# USART_LPUART.net
KiCad netlist of a schematic drawn in Altium Designer
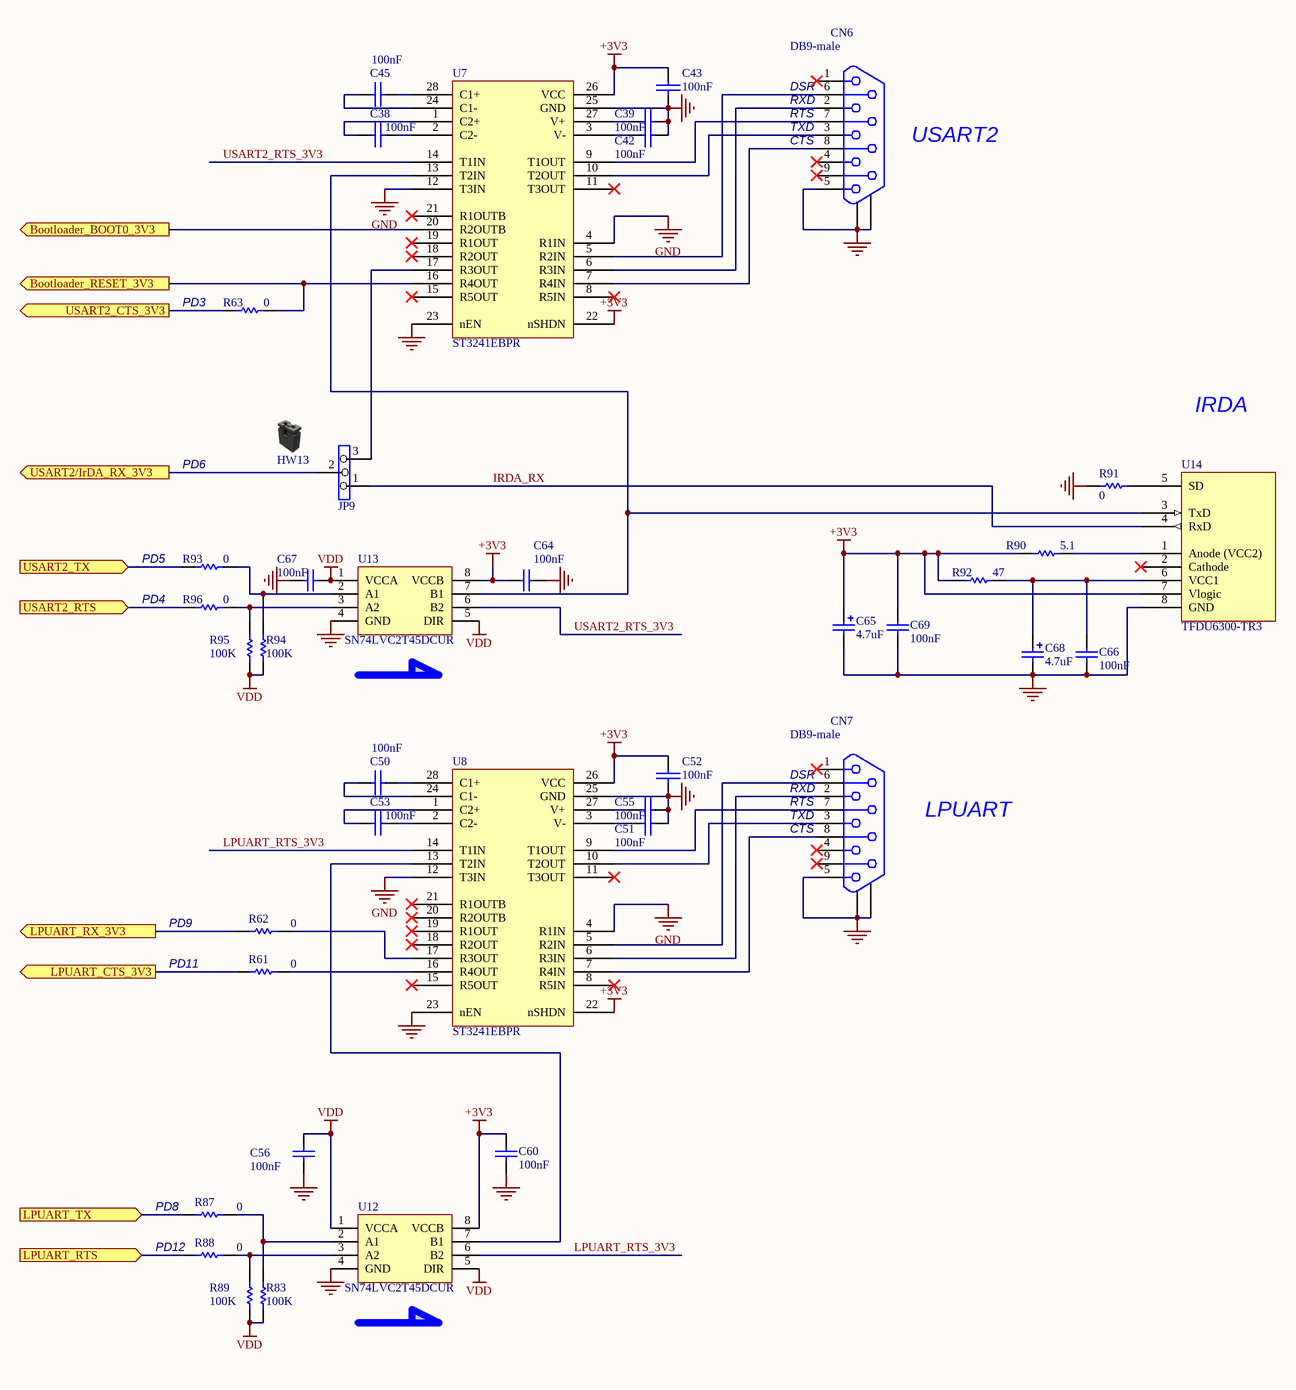
[diagram p0: USART_LPUART.SchDoc]

(export (version "E")
  (design (tool "Eeschema 10.0.6"))
  (components
    (comp (ref "C38")
      (value "100nF")
      (footprint "0402C")
      (description "Capacitor")
      (libsource (lib "*") (part "CAP"))
    )
    (comp (ref "C39")
      (value "100nF")
      (footprint "0402C")
      (description "Capacitor")
      (libsource (lib "*") (part "CAP"))
    )
    (comp (ref "C42")
      (value "100nF")
      (footprint "0402C")
      (description "Capacitor")
      (libsource (lib "*") (part "CAP"))
    )
    (comp (ref "C43")
      (value "100nF")
      (footprint "0402C")
      (description "Capacitor")
      (libsource (lib "*") (part "CAP"))
    )
    (comp (ref "C45")
      (value "100nF")
      (footprint "0402C")
      (description "Capacitor")
      (libsource (lib "*") (part "CAP"))
    )
    (comp (ref "C50")
      (value "100nF")
      (footprint "0402C")
      (description "Capacitor")
      (libsource (lib "*") (part "CAP"))
    )
    (comp (ref "C51")
      (value "100nF")
      (footprint "0402C")
      (description "Capacitor")
      (libsource (lib "*") (part "CAP"))
    )
    (comp (ref "C52")
      (value "100nF")
      (footprint "0402C")
      (description "Capacitor")
      (libsource (lib "*") (part "CAP"))
    )
    (comp (ref "C53")
      (value "100nF")
      (footprint "0402C")
      (description "Capacitor")
      (libsource (lib "*") (part "CAP"))
    )
    (comp (ref "C55")
      (value "100nF")
      (footprint "0402C")
      (description "Capacitor")
      (libsource (lib "*") (part "CAP"))
    )
    (comp (ref "C56")
      (value "100nF")
      (footprint "0402C")
      (description "Capacitor")
      (fields (field (name "PUBLISHER") "Altium Limited"))
      (libsource (lib "Miscellaneous Devices") (part "CAP"))
    )
    (comp (ref "C60")
      (value "100nF")
      (footprint "0402C")
      (description "Capacitor")
      (fields (field (name "PUBLISHER") "Altium Limited"))
      (libsource (lib "Miscellaneous Devices") (part "CAP"))
    )
    (comp (ref "C64")
      (value "100nF")
      (footprint "0402C")
      (description "Capacitor")
      (fields (field (name "PUBLISHER") "Altium Limited"))
      (libsource (lib "Miscellaneous Devices") (part "CAP"))
    )
    (comp (ref "C65")
      (value "4.7uF")
      (footprint "TAN-A")
      (description "Polarized Capacitor (Radial)")
      (fields (field (name "PUBLISHER") "Altium Limited"))
      (libsource (lib "Miscellaneous Devices") (part "Cap Pol1"))
    )
    (comp (ref "C66")
      (value "100nF")
      (footprint "0402C")
      (description "Capacitor")
      (fields (field (name "PUBLISHER") "Altium Limited"))
      (libsource (lib "Miscellaneous Devices") (part "CAP"))
    )
    (comp (ref "C67")
      (value "100nF")
      (footprint "0402C")
      (description "Capacitor")
      (fields (field (name "PUBLISHER") "Altium Limited"))
      (libsource (lib "Miscellaneous Devices") (part "CAP"))
    )
    (comp (ref "C68")
      (value "4.7uF")
      (footprint "TAN-A")
      (description "Polarized Capacitor (Radial)")
      (fields (field (name "PUBLISHER") "Altium Limited"))
      (libsource (lib "Miscellaneous Devices") (part "Cap Pol1"))
    )
    (comp (ref "C69")
      (value "100nF")
      (footprint "0402C")
      (description "Capacitor")
      (fields (field (name "PUBLISHER") "Altium Limited"))
      (libsource (lib "Miscellaneous Devices") (part "CAP"))
    )
    (comp (ref "CN6") (value "DB9-male") (footprint "DB9/M") (libsource (lib "MB1070") (part "DB9")))
    (comp (ref "CN7") (value "DB9-male") (footprint "DB9/M") (libsource (lib "MB1070") (part "DB9")))
    (comp (ref "HW13") (value "Shunt Black 2.54mm") (libsource (lib "MB1168") (part "Shunt Black 2.54mm")))
    (comp (ref "JP9") (value "~") (footprint "SIP3") (libsource (lib "STR910_SCHLIB") (part "Jumper3")))
    (comp (ref "R61")
      (value "0")
      (footprint "0603R")
      (description "Resistor")
      (fields (field (name "PUBLISHER") "Altium Limited"))
      (libsource (lib "Miscellaneous Devices") (part "Res1"))
    )
    (comp (ref "R62")
      (value "0")
      (footprint "0603R")
      (description "Resistor")
      (fields (field (name "PUBLISHER") "Altium Limited"))
      (libsource (lib "Miscellaneous Devices") (part "Res1"))
    )
    (comp (ref "R63")
      (value "0")
      (footprint "0603R")
      (description "Resistor")
      (fields (field (name "PUBLISHER") "Altium Limited"))
      (libsource (lib "Miscellaneous Devices") (part "Res1"))
    )
    (comp (ref "R83")
      (value "100K")
      (footprint "0402R")
      (description "Resistor")
      (fields (field (name "PUBLISHER") "Altium Limited"))
      (libsource (lib "Miscellaneous Devices") (part "Res1"))
    )
    (comp (ref "R87")
      (value "0")
      (footprint "0603R")
      (description "Resistor")
      (fields (field (name "PUBLISHER") "Altium Limited"))
      (libsource (lib "Miscellaneous Devices") (part "Res1"))
    )
    (comp (ref "R88")
      (value "0")
      (footprint "0603R")
      (description "Resistor")
      (fields (field (name "PUBLISHER") "Altium Limited"))
      (libsource (lib "Miscellaneous Devices") (part "Res1"))
    )
    (comp (ref "R89")
      (value "100K")
      (footprint "0402R")
      (description "Resistor")
      (fields (field (name "PUBLISHER") "Altium Limited"))
      (libsource (lib "Miscellaneous Devices") (part "Res1"))
    )
    (comp (ref "R90")
      (value "5.1")
      (footprint "0402R")
      (description "Resistor")
      (fields (field (name "PUBLISHER") "Altium Limited"))
      (libsource (lib "Miscellaneous Devices") (part "Res1"))
    )
    (comp (ref "R91")
      (value "0")
      (footprint "0603R")
      (description "Resistor")
      (fields (field (name "PUBLISHER") "Altium Limited"))
      (libsource (lib "Miscellaneous Devices") (part "Res1"))
    )
    (comp (ref "R92")
      (value "47")
      (footprint "0402R")
      (description "Resistor")
      (fields (field (name "PUBLISHER") "Altium Limited"))
      (libsource (lib "Miscellaneous Devices") (part "Res1"))
    )
    (comp (ref "R93")
      (value "0")
      (footprint "0603R")
      (description "Resistor")
      (fields (field (name "PUBLISHER") "Altium Limited"))
      (libsource (lib "Miscellaneous Devices") (part "Res1"))
    )
    (comp (ref "R94")
      (value "100K")
      (footprint "0402R")
      (description "Resistor")
      (fields (field (name "PUBLISHER") "Altium Limited"))
      (libsource (lib "Miscellaneous Devices") (part "Res1"))
    )
    (comp (ref "R95")
      (value "100K")
      (footprint "0402R")
      (description "Resistor")
      (fields (field (name "PUBLISHER") "Altium Limited"))
      (libsource (lib "Miscellaneous Devices") (part "Res1"))
    )
    (comp (ref "R96")
      (value "0")
      (footprint "0603R")
      (description "Resistor")
      (fields (field (name "PUBLISHER") "Altium Limited"))
      (libsource (lib "Miscellaneous Devices") (part "Res1"))
    )
    (comp (ref "U7")
      (value "ST3241EBPR")
      (footprint "SSOP28_0R65_10R2X7R8")
      (libsource (lib "*") (part "ST3241"))
    )
    (comp (ref "U8")
      (value "ST3241EBPR")
      (footprint "SSOP28_0R65_10R2X7R8")
      (libsource (lib "*") (part "ST3241"))
    )
    (comp (ref "U12")
      (value "SN74LVC2T45DCUR")
      (footprint "USOP8_0R5_2X3R1")
      (libsource (lib "MB818") (part "SN74LVC2T45DCUT"))
    )
    (comp (ref "U13")
      (value "SN74LVC2T45DCUR")
      (footprint "USOP8_0R5_2X3R1")
      (libsource (lib "MB818") (part "SN74LVC2T45DCUT"))
    )
    (comp (ref "U14")
      (value "TFDU6300-TR3")
      (footprint "IR_VISHAY3")
      (description "TFDU4300")
      (libsource (lib "*") (part "TFDU4300"))
    )
  )
  (nets
    (net (code "1") (name "+3V3") (class "Default")
      (node (ref "C43") (pin "2") (pinfunction "2_2") (pintype "passive"))
      (node (ref "C52") (pin "2") (pinfunction "2_2") (pintype "passive"))
      (node (ref "C60") (pin "2") (pinfunction "2_2") (pintype "passive"))
      (node (ref "C64") (pin "2") (pinfunction "2_2") (pintype "passive"))
      (node (ref "C65") (pin "1") (pinfunction "1_1") (pintype "passive"))
      (node (ref "C69") (pin "2") (pinfunction "2_2") (pintype "passive"))
      (node (ref "R90") (pin "1") (pinfunction "1_1") (pintype "passive"))
      (node (ref "R92") (pin "1") (pinfunction "1_1") (pintype "passive"))
      (node (ref "U12") (pin "8") (pinfunction "VCCB_8") (pintype "passive"))
      (node (ref "U13") (pin "8") (pinfunction "VCCB_8") (pintype "passive"))
      (node (ref "U14") (pin "7") (pinfunction "Vlogic_7") (pintype "passive"))
      (node (ref "U7") (pin "22") (pinfunction "nSHDN_22") (pintype "passive"))
      (node (ref "U7") (pin "26") (pinfunction "VCC_26") (pintype "passive"))
      (node (ref "U8") (pin "22") (pinfunction "nSHDN_22") (pintype "passive"))
      (node (ref "U8") (pin "26") (pinfunction "VCC_26") (pintype "passive"))
    )
    (net (code "2") (name "/Bootloader_BOOT0_3V3") (class "Default")
      (node (ref "U7") (pin "20") (pinfunction "R2OUTB_20") (pintype "passive"))
    )
    (net (code "3") (name "/Bootloader_RESET_3V3") (class "Default")
      (node (ref "R63") (pin "1") (pinfunction "1_1") (pintype "passive"))
      (node (ref "U7") (pin "16") (pinfunction "R4OUT_16") (pintype "passive"))
    )
    (net (code "4") (name "/IRDA_RX") (class "Default")
      (node (ref "JP9") (pin "1") (pintype "passive"))
      (node (ref "U14") (pin "4") (pinfunction "RxD_4") (pintype "output"))
    )
    (net (code "5") (name "/LPUART_CTS_3V3") (class "Default")
      (node (ref "R61") (pin "1") (pinfunction "1_1") (pintype "passive"))
    )
    (net (code "6") (name "/LPUART_RTS") (class "Default")
      (node (ref "R88") (pin "1") (pinfunction "1_1") (pintype "passive"))
    )
    (net (code "7") (name "/LPUART_RTS_3V3") (class "Default")
      (node (ref "U12") (pin "6") (pinfunction "B2_6") (pintype "passive"))
      (node (ref "U8") (pin "14") (pinfunction "T1IN_14") (pintype "passive"))
    )
    (net (code "8") (name "/LPUART_RX_3V3") (class "Default")
      (node (ref "R62") (pin "1") (pinfunction "1_1") (pintype "passive"))
    )
    (net (code "9") (name "/LPUART_TX") (class "Default")
      (node (ref "R87") (pin "1") (pinfunction "1_1") (pintype "passive"))
    )
    (net (code "10") (name "/USART2_CTS_3V3") (class "Default")
      (node (ref "R63") (pin "2") (pinfunction "2_2") (pintype "passive"))
    )
    (net (code "11") (name "/USART2_RTS") (class "Default")
      (node (ref "R96") (pin "2") (pinfunction "2_2") (pintype "passive"))
    )
    (net (code "12") (name "/USART2_RTS_3V3") (class "Default")
      (node (ref "U13") (pin "6") (pinfunction "B2_6") (pintype "passive"))
      (node (ref "U7") (pin "14") (pinfunction "T1IN_14") (pintype "passive"))
    )
    (net (code "13") (name "/USART2_TX") (class "Default")
      (node (ref "R93") (pin "2") (pinfunction "2_2") (pintype "passive"))
    )
    (net (code "14") (name "/USART2{slash}IrDA_RX_3V3") (class "Default")
      (node (ref "JP9") (pin "2") (pintype "passive"))
    )
    (net (code "15") (name "GND") (class "Default")
      (node (ref "C39") (pin "2") (pinfunction "2_2") (pintype "passive"))
      (node (ref "C42") (pin "2") (pinfunction "2_2") (pintype "passive"))
      (node (ref "C43") (pin "1") (pinfunction "1_1") (pintype "passive"))
      (node (ref "C51") (pin "2") (pinfunction "2_2") (pintype "passive"))
      (node (ref "C52") (pin "1") (pinfunction "1_1") (pintype "passive"))
      (node (ref "C55") (pin "2") (pinfunction "2_2") (pintype "passive"))
      (node (ref "C56") (pin "1") (pinfunction "1_1") (pintype "passive"))
      (node (ref "C60") (pin "1") (pinfunction "1_1") (pintype "passive"))
      (node (ref "C64") (pin "1") (pinfunction "1_1") (pintype "passive"))
      (node (ref "C65") (pin "2") (pinfunction "2_2") (pintype "passive"))
      (node (ref "C66") (pin "1") (pinfunction "1_1") (pintype "passive"))
      (node (ref "C67") (pin "1") (pinfunction "1_1") (pintype "passive"))
      (node (ref "C68") (pin "2") (pinfunction "2_2") (pintype "passive"))
      (node (ref "C69") (pin "1") (pinfunction "1_1") (pintype "passive"))
      (node (ref "CN6") (pin "10") (pinfunction "10_10") (pintype "passive"))
      (node (ref "CN6") (pin "11") (pinfunction "11_11") (pintype "passive"))
      (node (ref "CN6") (pin "5") (pinfunction "5_5") (pintype "passive"))
      (node (ref "CN7") (pin "10") (pinfunction "10_10") (pintype "passive"))
      (node (ref "CN7") (pin "11") (pinfunction "11_11") (pintype "passive"))
      (node (ref "CN7") (pin "5") (pinfunction "5_5") (pintype "passive"))
      (node (ref "R91") (pin "2") (pinfunction "2_2") (pintype "passive"))
      (node (ref "U12") (pin "4") (pinfunction "GND_4") (pintype "passive"))
      (node (ref "U13") (pin "4") (pinfunction "GND_4") (pintype "passive"))
      (node (ref "U14") (pin "8") (pinfunction "GND_8") (pintype "passive"))
      (node (ref "U7") (pin "12") (pinfunction "T3IN_12") (pintype "passive"))
      (node (ref "U7") (pin "23") (pinfunction "nEN_23") (pintype "passive"))
      (node (ref "U7") (pin "25") (pinfunction "GND_25") (pintype "passive"))
      (node (ref "U7") (pin "4") (pinfunction "R1IN_4") (pintype "passive"))
      (node (ref "U8") (pin "12") (pinfunction "T3IN_12") (pintype "passive"))
      (node (ref "U8") (pin "23") (pinfunction "nEN_23") (pintype "passive"))
      (node (ref "U8") (pin "25") (pinfunction "GND_25") (pintype "passive"))
      (node (ref "U8") (pin "4") (pinfunction "R1IN_4") (pintype "passive"))
    )
    (net (code "16") (name "Net-(U7-C1+)") (class "Default")
      (node (ref "C45") (pin "2") (pinfunction "2_2") (pintype "passive"))
      (node (ref "U7") (pin "28") (pinfunction "C1+_28") (pintype "passive"))
    )
    (net (code "17") (name "Net-(U7-C1-)") (class "Default")
      (node (ref "C45") (pin "1") (pinfunction "1_1") (pintype "passive"))
      (node (ref "U7") (pin "24") (pinfunction "C1-_24") (pintype "passive"))
    )
    (net (code "18") (name "Net-(U7-C2+)") (class "Default")
      (node (ref "C38") (pin "1") (pinfunction "1_1") (pintype "passive"))
      (node (ref "U7") (pin "1") (pinfunction "C2+_1") (pintype "passive"))
    )
    (net (code "19") (name "Net-(U7-C2-)") (class "Default")
      (node (ref "C38") (pin "2") (pinfunction "2_2") (pintype "passive"))
      (node (ref "U7") (pin "2") (pinfunction "C2-_2") (pintype "passive"))
    )
    (net (code "20") (name "Net-(U7-R2IN)") (class "Default")
      (node (ref "CN6") (pin "6") (pinfunction "6_6") (pintype "passive"))
      (node (ref "U7") (pin "5") (pinfunction "R2IN_5") (pintype "passive"))
    )
    (net (code "21") (name "Net-(U7-R3IN)") (class "Default")
      (node (ref "CN6") (pin "2") (pinfunction "2_2") (pintype "passive"))
      (node (ref "U7") (pin "6") (pinfunction "R3IN_6") (pintype "passive"))
    )
    (net (code "22") (name "Net-(U7-R3OUT)") (class "Default")
      (node (ref "JP9") (pin "3") (pintype "passive"))
      (node (ref "U7") (pin "17") (pinfunction "R3OUT_17") (pintype "passive"))
    )
    (net (code "23") (name "Net-(U7-R4IN)") (class "Default")
      (node (ref "CN6") (pin "8") (pinfunction "8_8") (pintype "passive"))
      (node (ref "U7") (pin "7") (pinfunction "R4IN_7") (pintype "passive"))
    )
    (net (code "24") (name "Net-(U7-T1OUT)") (class "Default")
      (node (ref "CN6") (pin "7") (pinfunction "7_7") (pintype "passive"))
      (node (ref "U7") (pin "9") (pinfunction "T1OUT_9") (pintype "passive"))
    )
    (net (code "25") (name "Net-(U7-T2OUT)") (class "Default")
      (node (ref "CN6") (pin "3") (pinfunction "3_3") (pintype "passive"))
      (node (ref "U7") (pin "10") (pinfunction "T2OUT_10") (pintype "passive"))
    )
    (net (code "26") (name "Net-(U7-V+)") (class "Default")
      (node (ref "C39") (pin "1") (pinfunction "1_1") (pintype "passive"))
      (node (ref "U7") (pin "27") (pinfunction "V+_27") (pintype "passive"))
    )
    (net (code "27") (name "Net-(U7-V-)") (class "Default")
      (node (ref "C42") (pin "1") (pinfunction "1_1") (pintype "passive"))
      (node (ref "U7") (pin "3") (pinfunction "V-_3") (pintype "passive"))
    )
    (net (code "28") (name "Net-(U8-C1+)") (class "Default")
      (node (ref "C50") (pin "2") (pinfunction "2_2") (pintype "passive"))
      (node (ref "U8") (pin "28") (pinfunction "C1+_28") (pintype "passive"))
    )
    (net (code "29") (name "Net-(U8-C1-)") (class "Default")
      (node (ref "C50") (pin "1") (pinfunction "1_1") (pintype "passive"))
      (node (ref "U8") (pin "24") (pinfunction "C1-_24") (pintype "passive"))
    )
    (net (code "30") (name "Net-(U8-C2+)") (class "Default")
      (node (ref "C53") (pin "1") (pinfunction "1_1") (pintype "passive"))
      (node (ref "U8") (pin "1") (pinfunction "C2+_1") (pintype "passive"))
    )
    (net (code "31") (name "Net-(U8-C2-)") (class "Default")
      (node (ref "C53") (pin "2") (pinfunction "2_2") (pintype "passive"))
      (node (ref "U8") (pin "2") (pinfunction "C2-_2") (pintype "passive"))
    )
    (net (code "32") (name "Net-(U8-R2IN)") (class "Default")
      (node (ref "CN7") (pin "6") (pinfunction "6_6") (pintype "passive"))
      (node (ref "U8") (pin "5") (pinfunction "R2IN_5") (pintype "passive"))
    )
    (net (code "33") (name "Net-(U8-R3IN)") (class "Default")
      (node (ref "CN7") (pin "2") (pinfunction "2_2") (pintype "passive"))
      (node (ref "U8") (pin "6") (pinfunction "R3IN_6") (pintype "passive"))
    )
    (net (code "34") (name "Net-(U8-R3OUT)") (class "Default")
      (node (ref "R62") (pin "2") (pinfunction "2_2") (pintype "passive"))
      (node (ref "U8") (pin "17") (pinfunction "R3OUT_17") (pintype "passive"))
    )
    (net (code "35") (name "Net-(U8-R4IN)") (class "Default")
      (node (ref "CN7") (pin "8") (pinfunction "8_8") (pintype "passive"))
      (node (ref "U8") (pin "7") (pinfunction "R4IN_7") (pintype "passive"))
    )
    (net (code "36") (name "Net-(U8-R4OUT)") (class "Default")
      (node (ref "R61") (pin "2") (pinfunction "2_2") (pintype "passive"))
      (node (ref "U8") (pin "16") (pinfunction "R4OUT_16") (pintype "passive"))
    )
    (net (code "37") (name "Net-(U8-T1OUT)") (class "Default")
      (node (ref "CN7") (pin "7") (pinfunction "7_7") (pintype "passive"))
      (node (ref "U8") (pin "9") (pinfunction "T1OUT_9") (pintype "passive"))
    )
    (net (code "38") (name "Net-(U8-T2OUT)") (class "Default")
      (node (ref "CN7") (pin "3") (pinfunction "3_3") (pintype "passive"))
      (node (ref "U8") (pin "10") (pinfunction "T2OUT_10") (pintype "passive"))
    )
    (net (code "39") (name "Net-(U8-V+)") (class "Default")
      (node (ref "C55") (pin "1") (pinfunction "1_1") (pintype "passive"))
      (node (ref "U8") (pin "27") (pinfunction "V+_27") (pintype "passive"))
    )
    (net (code "40") (name "Net-(U8-V-)") (class "Default")
      (node (ref "C51") (pin "1") (pinfunction "1_1") (pintype "passive"))
      (node (ref "U8") (pin "3") (pinfunction "V-_3") (pintype "passive"))
    )
    (net (code "41") (name "Net-(U12-A1)") (class "Default")
      (node (ref "R83") (pin "1") (pinfunction "1_1") (pintype "passive"))
      (node (ref "R87") (pin "2") (pinfunction "2_2") (pintype "passive"))
      (node (ref "U12") (pin "2") (pinfunction "A1_2") (pintype "passive"))
    )
    (net (code "42") (name "Net-(U12-A2)") (class "Default")
      (node (ref "R88") (pin "2") (pinfunction "2_2") (pintype "passive"))
      (node (ref "R89") (pin "1") (pinfunction "1_1") (pintype "passive"))
      (node (ref "U12") (pin "3") (pinfunction "A2_3") (pintype "passive"))
    )
    (net (code "43") (name "Net-(U12-B1)") (class "Default")
      (node (ref "U12") (pin "7") (pinfunction "B1_7") (pintype "passive"))
      (node (ref "U8") (pin "13") (pinfunction "T2IN_13") (pintype "passive"))
    )
    (net (code "44") (name "Net-(U13-A1)") (class "Default")
      (node (ref "R93") (pin "1") (pinfunction "1_1") (pintype "passive"))
      (node (ref "R94") (pin "1") (pinfunction "1_1") (pintype "passive"))
      (node (ref "U13") (pin "2") (pinfunction "A1_2") (pintype "passive"))
    )
    (net (code "45") (name "Net-(U13-A2)") (class "Default")
      (node (ref "R95") (pin "1") (pinfunction "1_1") (pintype "passive"))
      (node (ref "R96") (pin "1") (pinfunction "1_1") (pintype "passive"))
      (node (ref "U13") (pin "3") (pinfunction "A2_3") (pintype "passive"))
    )
    (net (code "46") (name "Net-(U13-B1)") (class "Default")
      (node (ref "U13") (pin "7") (pinfunction "B1_7") (pintype "passive"))
      (node (ref "U14") (pin "3") (pinfunction "TxD_3") (pintype "input"))
      (node (ref "U7") (pin "13") (pinfunction "T2IN_13") (pintype "passive"))
    )
    (net (code "47") (name "Net-(U14-Anode_(VCC2))") (class "Default")
      (node (ref "R90") (pin "2") (pinfunction "2_2") (pintype "passive"))
      (node (ref "U14") (pin "1") (pinfunction "Anode_(VCC2)_1") (pintype "passive"))
    )
    (net (code "48") (name "Net-(U14-SD)") (class "Default")
      (node (ref "R91") (pin "1") (pinfunction "1_1") (pintype "passive"))
      (node (ref "U14") (pin "5") (pinfunction "SD_5") (pintype "passive"))
    )
    (net (code "49") (name "Net-(U14-VCC1)") (class "Default")
      (node (ref "C66") (pin "2") (pinfunction "2_2") (pintype "passive"))
      (node (ref "C68") (pin "1") (pinfunction "1_1") (pintype "passive"))
      (node (ref "R92") (pin "2") (pinfunction "2_2") (pintype "passive"))
      (node (ref "U14") (pin "6") (pinfunction "VCC1_6") (pintype "passive"))
    )
    (net (code "50") (name "VDD") (class "Default")
      (node (ref "C56") (pin "2") (pinfunction "2_2") (pintype "passive"))
      (node (ref "C67") (pin "2") (pinfunction "2_2") (pintype "passive"))
      (node (ref "R83") (pin "2") (pinfunction "2_2") (pintype "passive"))
      (node (ref "R89") (pin "2") (pinfunction "2_2") (pintype "passive"))
      (node (ref "R94") (pin "2") (pinfunction "2_2") (pintype "passive"))
      (node (ref "R95") (pin "2") (pinfunction "2_2") (pintype "passive"))
      (node (ref "U12") (pin "1") (pinfunction "VCCA_1") (pintype "passive"))
      (node (ref "U12") (pin "5") (pinfunction "DIR_5") (pintype "passive"))
      (node (ref "U13") (pin "1") (pinfunction "VCCA_1") (pintype "passive"))
      (node (ref "U13") (pin "5") (pinfunction "DIR_5") (pintype "passive"))
    )
    (net (code "51") (name "unconnected-(CN6-Pad1)") (class "Default")
      (node (ref "CN6") (pin "1") (pinfunction "1_1") (pintype "passive+no_connect"))
    )
    (net (code "52") (name "unconnected-(CN6-Pad4)") (class "Default")
      (node (ref "CN6") (pin "4") (pinfunction "4_4") (pintype "passive+no_connect"))
    )
    (net (code "53") (name "unconnected-(CN6-Pad9)") (class "Default")
      (node (ref "CN6") (pin "9") (pinfunction "9_9") (pintype "passive+no_connect"))
    )
    (net (code "54") (name "unconnected-(CN7-Pad1)") (class "Default")
      (node (ref "CN7") (pin "1") (pinfunction "1_1") (pintype "passive+no_connect"))
    )
    (net (code "55") (name "unconnected-(CN7-Pad4)") (class "Default")
      (node (ref "CN7") (pin "4") (pinfunction "4_4") (pintype "passive+no_connect"))
    )
    (net (code "56") (name "unconnected-(CN7-Pad9)") (class "Default")
      (node (ref "CN7") (pin "9") (pinfunction "9_9") (pintype "passive+no_connect"))
    )
    (net (code "57") (name "unconnected-(U7-R1OUT-Pad19)") (class "Default")
      (node (ref "U7") (pin "19") (pinfunction "R1OUT_19") (pintype "passive+no_connect"))
    )
    (net (code "58") (name "unconnected-(U7-R1OUTB-Pad21)") (class "Default")
      (node (ref "U7") (pin "21") (pinfunction "R1OUTB_21") (pintype "passive+no_connect"))
    )
    (net (code "59") (name "unconnected-(U7-R2OUT-Pad18)") (class "Default")
      (node (ref "U7") (pin "18") (pinfunction "R2OUT_18") (pintype "passive+no_connect"))
    )
    (net (code "60") (name "unconnected-(U7-R5IN-Pad8)") (class "Default")
      (node (ref "U7") (pin "8") (pinfunction "R5IN_8") (pintype "passive+no_connect"))
    )
    (net (code "61") (name "unconnected-(U7-R5OUT-Pad15)") (class "Default")
      (node (ref "U7") (pin "15") (pinfunction "R5OUT_15") (pintype "passive+no_connect"))
    )
    (net (code "62") (name "unconnected-(U7-T3OUT-Pad11)") (class "Default")
      (node (ref "U7") (pin "11") (pinfunction "T3OUT_11") (pintype "passive+no_connect"))
    )
    (net (code "63") (name "unconnected-(U8-R1OUT-Pad19)") (class "Default")
      (node (ref "U8") (pin "19") (pinfunction "R1OUT_19") (pintype "passive+no_connect"))
    )
    (net (code "64") (name "unconnected-(U8-R1OUTB-Pad21)") (class "Default")
      (node (ref "U8") (pin "21") (pinfunction "R1OUTB_21") (pintype "passive+no_connect"))
    )
    (net (code "65") (name "unconnected-(U8-R2OUT-Pad18)") (class "Default")
      (node (ref "U8") (pin "18") (pinfunction "R2OUT_18") (pintype "passive+no_connect"))
    )
    (net (code "66") (name "unconnected-(U8-R2OUTB-Pad20)") (class "Default")
      (node (ref "U8") (pin "20") (pinfunction "R2OUTB_20") (pintype "passive+no_connect"))
    )
    (net (code "67") (name "unconnected-(U8-R5IN-Pad8)") (class "Default")
      (node (ref "U8") (pin "8") (pinfunction "R5IN_8") (pintype "passive+no_connect"))
    )
    (net (code "68") (name "unconnected-(U8-R5OUT-Pad15)") (class "Default")
      (node (ref "U8") (pin "15") (pinfunction "R5OUT_15") (pintype "passive+no_connect"))
    )
    (net (code "69") (name "unconnected-(U8-T3OUT-Pad11)") (class "Default")
      (node (ref "U8") (pin "11") (pinfunction "T3OUT_11") (pintype "passive+no_connect"))
    )
    (net (code "70") (name "unconnected-(U14-Cathode-Pad2)") (class "Default")
      (node (ref "U14") (pin "2") (pinfunction "Cathode_2") (pintype "passive+no_connect"))
    )
  )
)
